# SD.net
KiCad netlist of a schematic drawn in Altium Designer
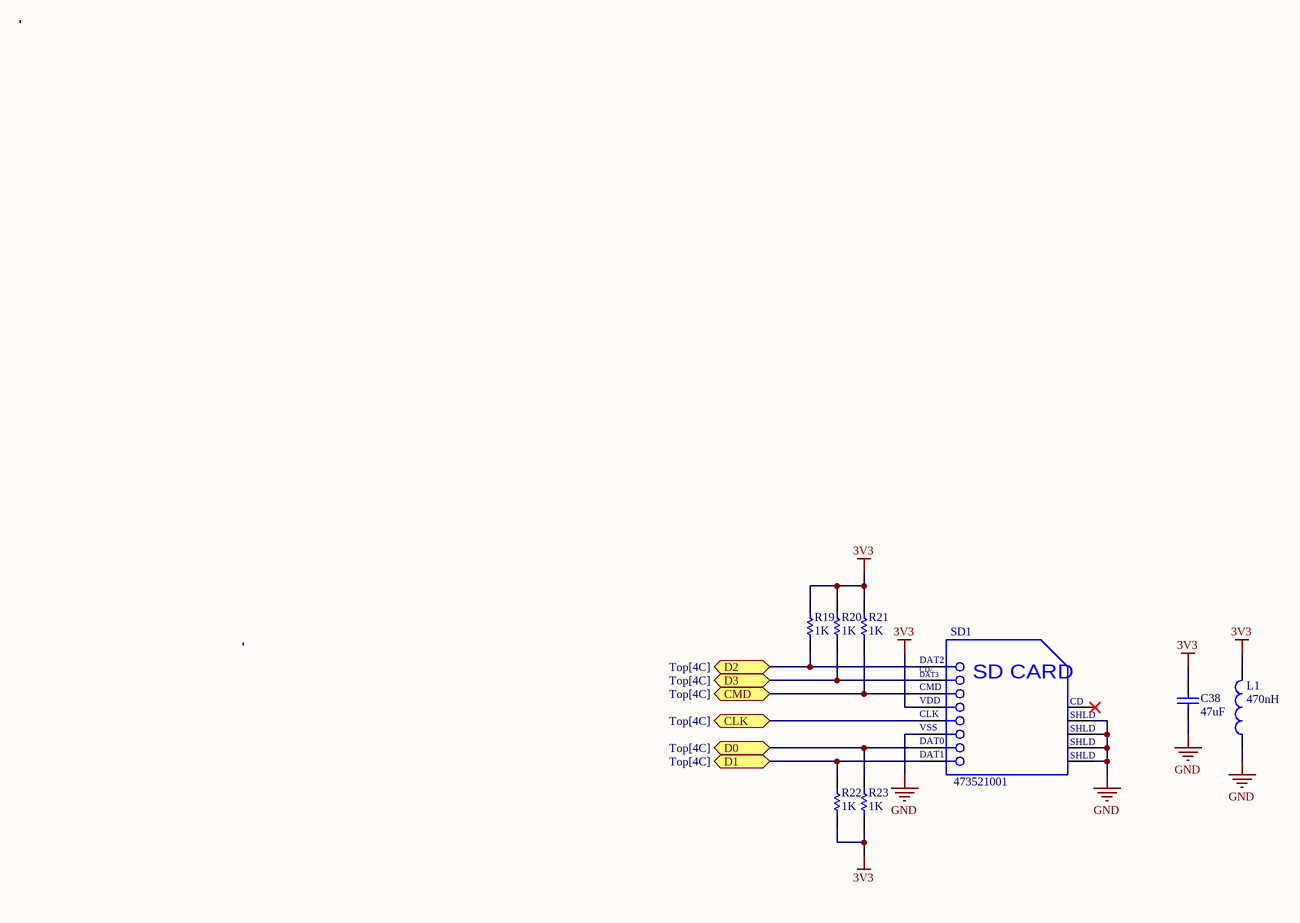
[diagram p0: SD.SchDoc]

(export (version "E")
  (design (tool "Eeschema 10.0.6"))
  (components
    (comp (ref "C38")
      (value "47uF")
      (description "Capacitor")
      (libsource (lib "Simulation Generic Components") (part "Capacitor"))
    )
    (comp (ref "L1")
      (value "470nH")
      (description "Inductor")
      (libsource (lib "Simulation Generic Components") (part "Inductor"))
    )
    (comp (ref "R19")
      (value "1K")
      (description "Resistor")
      (libsource (lib "Simulation Generic Components") (part "Resistor"))
    )
    (comp (ref "R20")
      (value "1K")
      (description "Resistor")
      (libsource (lib "Simulation Generic Components") (part "Resistor"))
    )
    (comp (ref "R21")
      (value "1K")
      (description "Resistor")
      (libsource (lib "Simulation Generic Components") (part "Resistor"))
    )
    (comp (ref "R22")
      (value "1K")
      (description "Resistor")
      (libsource (lib "Simulation Generic Components") (part "Resistor"))
    )
    (comp (ref "R23")
      (value "1K")
      (description "Resistor")
      (libsource (lib "Simulation Generic Components") (part "Resistor"))
    )
    (comp (ref "SD1")
      (value "473521001")
      (footprint "MOLX-473521001_V")
      (description "MicroSD(TM), Pitch 1.1 mm, 8 Position, Height 1.88 mm, -20 to 85 degC, RoHS, Tape and Reel")
      (fields (field (name "MANUFACTURER") "Molex"))
      (libsource (lib "Altium Content Vault") (part "CN-SD-8-1SW-4S"))
    )
  )
  (nets
    (net (code "1") (name "/CLK") (class "Default")
      (node (ref "SD1") (pin "5") (pinfunction "CLK_5") (pintype "passive"))
    )
    (net (code "2") (name "/CMD") (class "Default")
      (node (ref "R21") (pin "1") (pinfunction "1_1") (pintype "passive"))
      (node (ref "SD1") (pin "3") (pinfunction "CMD_3") (pintype "passive"))
    )
    (net (code "3") (name "/D0") (class "Default")
      (node (ref "R23") (pin "2") (pinfunction "2_2") (pintype "passive"))
      (node (ref "SD1") (pin "7") (pinfunction "DAT0_7") (pintype "passive"))
    )
    (net (code "4") (name "/D1") (class "Default")
      (node (ref "R22") (pin "2") (pinfunction "2_2") (pintype "passive"))
      (node (ref "SD1") (pin "8") (pinfunction "DAT1_8") (pintype "passive"))
    )
    (net (code "5") (name "/D2") (class "Default")
      (node (ref "R19") (pin "1") (pinfunction "1_1") (pintype "passive"))
      (node (ref "SD1") (pin "1") (pinfunction "DAT2_1") (pintype "passive"))
    )
    (net (code "6") (name "/D3") (class "Default")
      (node (ref "R20") (pin "1") (pinfunction "1_1") (pintype "passive"))
      (node (ref "SD1") (pin "2") (pinfunction "CD/DAT3_2") (pintype "passive"))
    )
    (net (code "7") (name "3V3") (class "Default")
      (node (ref "C38") (pin "2") (pinfunction "2_2") (pintype "passive"))
      (node (ref "L1") (pin "2") (pinfunction "2_2") (pintype "passive"))
      (node (ref "R19") (pin "2") (pinfunction "2_2") (pintype "passive"))
      (node (ref "R20") (pin "2") (pinfunction "2_2") (pintype "passive"))
      (node (ref "R21") (pin "2") (pinfunction "2_2") (pintype "passive"))
      (node (ref "R22") (pin "1") (pinfunction "1_1") (pintype "passive"))
      (node (ref "R23") (pin "1") (pinfunction "1_1") (pintype "passive"))
      (node (ref "SD1") (pin "4") (pinfunction "VDD_4") (pintype "passive"))
    )
    (net (code "8") (name "GND") (class "Default")
      (node (ref "C38") (pin "1") (pinfunction "1_1") (pintype "passive"))
      (node (ref "L1") (pin "1") (pinfunction "1_1") (pintype "passive"))
      (node (ref "SD1") (pin "10") (pinfunction "SHLD_10") (pintype "passive"))
      (node (ref "SD1") (pin "11") (pinfunction "SHLD_11") (pintype "passive"))
      (node (ref "SD1") (pin "12") (pinfunction "SHLD_12") (pintype "passive"))
      (node (ref "SD1") (pin "13") (pinfunction "SHLD_13") (pintype "passive"))
      (node (ref "SD1") (pin "6") (pinfunction "VSS_6") (pintype "passive"))
    )
    (net (code "9") (name "unconnected-(SD1-CD-Pad9)") (class "Default")
      (node (ref "SD1") (pin "9") (pinfunction "CD_9") (pintype "passive+no_connect"))
    )
  )
)
